# Lora-ver1_0.net
KiCad netlist of a schematic drawn in Altium Designer
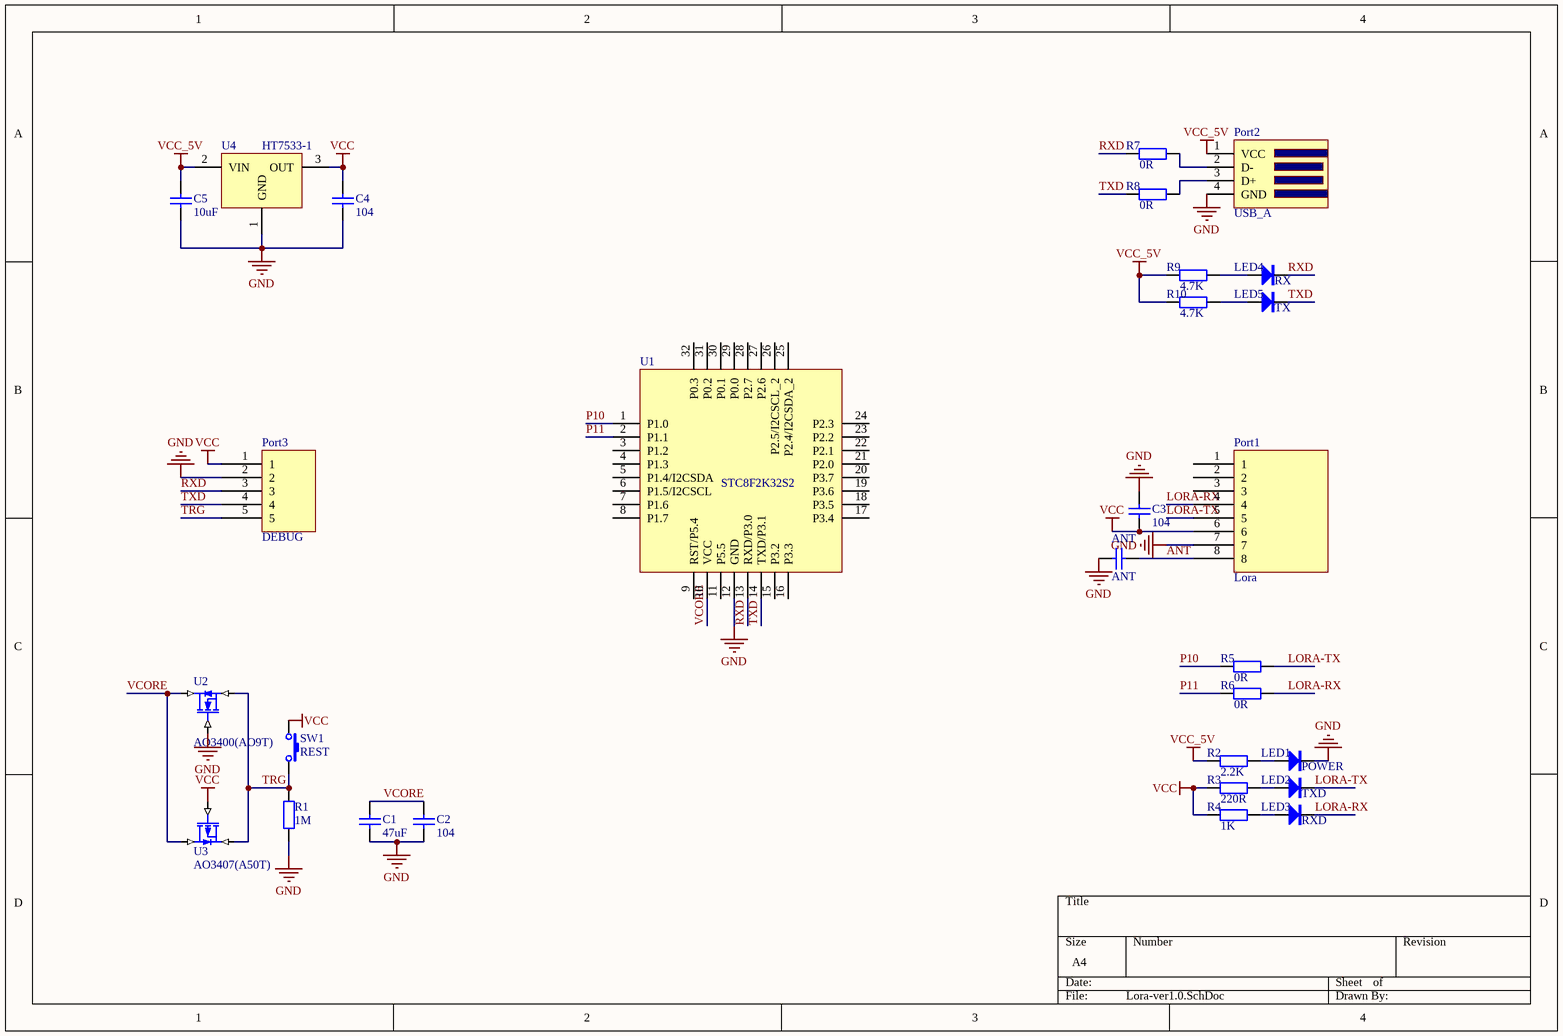
[diagram p0: Lora-ver1.0.SchDoc]

(export (version "E")
  (design (tool "Eeschema 10.0.6"))
  (components
    (comp (ref "ANT")
      (value "ANT")
      (footprint "SWA-KE天线母座")
      (description "Capacitor")
      (fields (field (name "PUBLISHER") "Altium Limited"))
      (libsource (lib "Miscellaneous Devices") (part "Cap"))
    )
    (comp (ref "C1")
      (value "47uF")
      (footprint "0603")
      (description "Capacitor")
      (fields (field (name "PUBLISHER") "Altium Limited"))
      (libsource (lib "Miscellaneous Devices") (part "Cap"))
    )
    (comp (ref "C2")
      (value "104")
      (footprint "0603")
      (description "Capacitor")
      (fields (field (name "PUBLISHER") "Altium Limited"))
      (libsource (lib "Miscellaneous Devices") (part "Cap"))
    )
    (comp (ref "C3")
      (value "104")
      (footprint "0603")
      (description "Capacitor")
      (fields (field (name "PUBLISHER") "Altium Limited"))
      (libsource (lib "Miscellaneous Devices") (part "Cap"))
    )
    (comp (ref "C4")
      (value "104")
      (footprint "0603")
      (description "Capacitor")
      (fields (field (name "PUBLISHER") "Altium Limited"))
      (libsource (lib "Miscellaneous Devices") (part "Cap"))
    )
    (comp (ref "C5")
      (value "10uF")
      (footprint "0603")
      (description "Capacitor")
      (fields (field (name "PUBLISHER") "Altium Limited"))
      (libsource (lib "Miscellaneous Devices") (part "Cap"))
    )
    (comp (ref "LED1")
      (value "POWER")
      (footprint "2.54LED")
      (description "diode")
      (libsource (lib "dajiang SCH -DXP") (part "DIODE"))
    )
    (comp (ref "LED2")
      (value "TXD")
      (footprint "2.54LED")
      (description "diode")
      (libsource (lib "dajiang SCH -DXP") (part "DIODE"))
    )
    (comp (ref "LED3")
      (value "RXD")
      (footprint "2.54LED")
      (description "diode")
      (libsource (lib "dajiang SCH -DXP") (part "DIODE"))
    )
    (comp (ref "LED4")
      (value "RX")
      (footprint "LED-0603")
      (description "diode")
      (libsource (lib "dajiang SCH -DXP") (part "DIODE"))
    )
    (comp (ref "LED5")
      (value "TX")
      (footprint "LED-0603")
      (description "diode")
      (libsource (lib "dajiang SCH -DXP") (part "DIODE"))
    )
    (comp (ref "Port1") (value "Lora") (footprint "LoRa_Usart") (libsource (lib "MYSHC") (part "Lora")))
    (comp (ref "Port2") (value "USB_A") (footprint "USB-A") (libsource (lib "mylib") (part "USB")))
    (comp (ref "Port3") (value "DEBUG") (footprint "STC_DEBUG") (libsource (lib "MYSHC") (part "PIN-5")))
    (comp (ref "R1")
      (value "1M")
      (footprint "0603")
      (description "Resistor")
      (fields (field (name "PUBLISHER") "Altium Limited"))
      (libsource (lib "") (part "Res2_1"))
    )
    (comp (ref "R2")
      (value "2.2K")
      (footprint "0603")
      (description "Resistor")
      (fields (field (name "PUBLISHER") "Altium Limited"))
      (libsource (lib "Miscellaneous Devices") (part "Res2"))
    )
    (comp (ref "R3")
      (value "220R")
      (footprint "0603")
      (description "Resistor")
      (fields (field (name "PUBLISHER") "Altium Limited"))
      (libsource (lib "Miscellaneous Devices") (part "Res2"))
    )
    (comp (ref "R4")
      (value "1K")
      (footprint "0603")
      (description "Resistor")
      (fields (field (name "PUBLISHER") "Altium Limited"))
      (libsource (lib "Miscellaneous Devices") (part "Res2"))
    )
    (comp (ref "R5")
      (value "0R")
      (footprint "0603")
      (description "Resistor")
      (fields (field (name "PUBLISHER") "Altium Limited"))
      (libsource (lib "Miscellaneous Devices") (part "Res2"))
    )
    (comp (ref "R6")
      (value "0R")
      (footprint "0603")
      (description "Resistor")
      (fields (field (name "PUBLISHER") "Altium Limited"))
      (libsource (lib "Miscellaneous Devices") (part "Res2"))
    )
    (comp (ref "R7")
      (value "0R")
      (footprint "0603")
      (description "Resistor")
      (fields (field (name "PUBLISHER") "Altium Limited"))
      (libsource (lib "Miscellaneous Devices") (part "Res2"))
    )
    (comp (ref "R8")
      (value "0R")
      (footprint "0603")
      (description "Resistor")
      (fields (field (name "PUBLISHER") "Altium Limited"))
      (libsource (lib "Miscellaneous Devices") (part "Res2"))
    )
    (comp (ref "R9")
      (value "4.7K")
      (footprint "0603")
      (description "Resistor")
      (fields (field (name "PUBLISHER") "Altium Limited"))
      (libsource (lib "Miscellaneous Devices") (part "Res2"))
    )
    (comp (ref "R10")
      (value "4.7K")
      (footprint "0603")
      (description "Resistor")
      (fields (field (name "PUBLISHER") "Altium Limited"))
      (libsource (lib "Miscellaneous Devices") (part "Res2"))
    )
    (comp (ref "SW1")
      (value "REST")
      (footprint "SW-1")
      (description "key")
      (libsource (lib "dajiang SCH -DXP") (part "SW-P"))
    )
    (comp (ref "U1")
      (value "STC8F2K32S2")
      (footprint "LQPF-32")
      (libsource (lib "mylib") (part "STC8F2K64S2"))
    )
    (comp (ref "U2")
      (value "AO3400(AO9T)")
      (footprint "SOT-23")
      (description "mosfet")
      (libsource (lib "dajiang SCH -DXP") (part "MOSFET-N"))
    )
    (comp (ref "U3")
      (value "AO3407(A50T)")
      (footprint "SOT-23")
      (description "mosfet")
      (libsource (lib "dajiang SCH -DXP") (part "MOSFET-P"))
    )
    (comp (ref "U4") (value "HT7533-1") (footprint "3A5A3D") (libsource (lib "mylib") (part "HT7533-1")))
  )
  (nets
    (net (code "1") (name "/ANT") (class "Default")
      (node (ref "ANT") (pin "1") (pinfunction "1_1") (pintype "passive"))
      (node (ref "Port1") (pin "8") (pinfunction "8_8") (pintype "passive"))
    )
    (net (code "2") (name "/LORA-RX") (class "Default")
      (node (ref "LED3") (pin "2") (pinfunction "2_2") (pintype "passive"))
      (node (ref "Port1") (pin "4") (pinfunction "4_4") (pintype "passive"))
      (node (ref "R6") (pin "1") (pinfunction "1_1") (pintype "passive"))
    )
    (net (code "3") (name "/LORA-TX") (class "Default")
      (node (ref "LED2") (pin "2") (pinfunction "2_2") (pintype "passive"))
      (node (ref "Port1") (pin "5") (pinfunction "5_5") (pintype "passive"))
      (node (ref "R5") (pin "1") (pinfunction "1_1") (pintype "passive"))
    )
    (net (code "4") (name "/P10") (class "Default")
      (node (ref "R5") (pin "2") (pinfunction "2_2") (pintype "passive"))
      (node (ref "U1") (pin "1") (pinfunction "P1.0_1") (pintype "passive"))
    )
    (net (code "5") (name "/P11") (class "Default")
      (node (ref "R6") (pin "2") (pinfunction "2_2") (pintype "passive"))
      (node (ref "U1") (pin "2") (pinfunction "P1.1_2") (pintype "passive"))
    )
    (net (code "6") (name "/RXD") (class "Default")
      (node (ref "LED4") (pin "2") (pinfunction "2_2") (pintype "passive"))
      (node (ref "Port3") (pin "3") (pinfunction "3_3") (pintype "passive"))
      (node (ref "R7") (pin "2") (pinfunction "2_2") (pintype "passive"))
      (node (ref "U1") (pin "13") (pinfunction "RXD/P3.0_13") (pintype "passive"))
    )
    (net (code "7") (name "/TRG") (class "Default")
      (node (ref "Port3") (pin "5") (pinfunction "5_5") (pintype "passive"))
      (node (ref "R1") (pin "2") (pinfunction "2_2") (pintype "passive"))
      (node (ref "SW1") (pin "2") (pinfunction "2_2") (pintype "passive"))
      (node (ref "U2") (pin "2") (pinfunction "D_2") (pintype "input"))
      (node (ref "U3") (pin "2") (pinfunction "S_2") (pintype "input"))
    )
    (net (code "8") (name "/TXD") (class "Default")
      (node (ref "LED5") (pin "2") (pinfunction "2_2") (pintype "passive"))
      (node (ref "Port3") (pin "4") (pinfunction "4_4") (pintype "passive"))
      (node (ref "R8") (pin "2") (pinfunction "2_2") (pintype "passive"))
      (node (ref "U1") (pin "14") (pinfunction "TXD/P3.1_14") (pintype "passive"))
    )
    (net (code "9") (name "/VCORE") (class "Default")
      (node (ref "C1") (pin "2") (pinfunction "2_2") (pintype "passive"))
      (node (ref "C2") (pin "2") (pinfunction "2_2") (pintype "passive"))
      (node (ref "U1") (pin "10") (pinfunction "VCC_10") (pintype "passive"))
      (node (ref "U2") (pin "3") (pinfunction "S_3") (pintype "input"))
      (node (ref "U3") (pin "3") (pinfunction "D_3") (pintype "input"))
    )
    (net (code "10") (name "GND") (class "Default")
      (node (ref "ANT") (pin "2") (pinfunction "2_2") (pintype "passive"))
      (node (ref "C1") (pin "1") (pinfunction "1_1") (pintype "passive"))
      (node (ref "C2") (pin "1") (pinfunction "1_1") (pintype "passive"))
      (node (ref "C3") (pin "1") (pinfunction "1_1") (pintype "passive"))
      (node (ref "C4") (pin "2") (pinfunction "2_2") (pintype "passive"))
      (node (ref "C5") (pin "2") (pinfunction "2_2") (pintype "passive"))
      (node (ref "LED1") (pin "2") (pinfunction "2_2") (pintype "passive"))
      (node (ref "Port1") (pin "7") (pinfunction "7_7") (pintype "passive"))
      (node (ref "Port2") (pin "4") (pinfunction "GND_4") (pintype "passive"))
      (node (ref "Port3") (pin "2") (pinfunction "2_2") (pintype "passive"))
      (node (ref "R1") (pin "1") (pinfunction "1_1") (pintype "passive"))
      (node (ref "U1") (pin "12") (pinfunction "GND_12") (pintype "passive"))
      (node (ref "U2") (pin "1") (pinfunction "G_1") (pintype "input"))
      (node (ref "U4") (pin "1") (pinfunction "GND_1") (pintype "passive"))
    )
    (net (code "11") (name "Net-(LED1-Pad1)") (class "Default")
      (node (ref "LED1") (pin "1") (pinfunction "1_1") (pintype "passive"))
      (node (ref "R2") (pin "1") (pinfunction "1_1") (pintype "passive"))
    )
    (net (code "12") (name "Net-(LED2-Pad1)") (class "Default")
      (node (ref "LED2") (pin "1") (pinfunction "1_1") (pintype "passive"))
      (node (ref "R3") (pin "1") (pinfunction "1_1") (pintype "passive"))
    )
    (net (code "13") (name "Net-(LED3-Pad1)") (class "Default")
      (node (ref "LED3") (pin "1") (pinfunction "1_1") (pintype "passive"))
      (node (ref "R4") (pin "1") (pinfunction "1_1") (pintype "passive"))
    )
    (net (code "14") (name "Net-(LED4-Pad1)") (class "Default")
      (node (ref "LED4") (pin "1") (pinfunction "1_1") (pintype "passive"))
      (node (ref "R9") (pin "1") (pinfunction "1_1") (pintype "passive"))
    )
    (net (code "15") (name "Net-(LED5-Pad1)") (class "Default")
      (node (ref "LED5") (pin "1") (pinfunction "1_1") (pintype "passive"))
      (node (ref "R10") (pin "1") (pinfunction "1_1") (pintype "passive"))
    )
    (net (code "16") (name "Net-(Port2-D+)") (class "Default")
      (node (ref "Port2") (pin "3") (pinfunction "D+_3") (pintype "passive"))
      (node (ref "R8") (pin "1") (pinfunction "1_1") (pintype "passive"))
    )
    (net (code "17") (name "Net-(Port2-D-)") (class "Default")
      (node (ref "Port2") (pin "2") (pinfunction "D-_2") (pintype "passive"))
      (node (ref "R7") (pin "1") (pinfunction "1_1") (pintype "passive"))
    )
    (net (code "18") (name "VCC") (class "Default")
      (node (ref "C3") (pin "2") (pinfunction "2_2") (pintype "passive"))
      (node (ref "C4") (pin "1") (pinfunction "1_1") (pintype "passive"))
      (node (ref "Port1") (pin "6") (pinfunction "6_6") (pintype "passive"))
      (node (ref "Port3") (pin "1") (pinfunction "1_1") (pintype "passive"))
      (node (ref "R3") (pin "2") (pinfunction "2_2") (pintype "passive"))
      (node (ref "R4") (pin "2") (pinfunction "2_2") (pintype "passive"))
      (node (ref "SW1") (pin "1") (pinfunction "1_1") (pintype "passive"))
      (node (ref "U3") (pin "1") (pinfunction "G_1") (pintype "input"))
      (node (ref "U4") (pin "3") (pinfunction "OUT_3") (pintype "passive"))
    )
    (net (code "19") (name "VCC_5V") (class "Default")
      (node (ref "C5") (pin "1") (pinfunction "1_1") (pintype "passive"))
      (node (ref "Port2") (pin "1") (pinfunction "VCC_1") (pintype "passive"))
      (node (ref "R10") (pin "2") (pinfunction "2_2") (pintype "passive"))
      (node (ref "R2") (pin "2") (pinfunction "2_2") (pintype "passive"))
      (node (ref "R9") (pin "2") (pinfunction "2_2") (pintype "passive"))
      (node (ref "U4") (pin "2") (pinfunction "VIN_2") (pintype "passive"))
    )
    (net (code "20") (name "unconnected-(Port1-Pad1)") (class "Default")
      (node (ref "Port1") (pin "1") (pinfunction "1_1") (pintype "passive"))
    )
    (net (code "21") (name "unconnected-(Port1-Pad2)") (class "Default")
      (node (ref "Port1") (pin "2") (pinfunction "2_2") (pintype "passive"))
    )
    (net (code "22") (name "unconnected-(Port1-Pad3)") (class "Default")
      (node (ref "Port1") (pin "3") (pinfunction "3_3") (pintype "passive"))
    )
    (net (code "23") (name "unconnected-(U1-P0.0-Pad29)") (class "Default")
      (node (ref "U1") (pin "29") (pinfunction "P0.0_29") (pintype "passive"))
    )
    (net (code "24") (name "unconnected-(U1-P0.1-Pad30)") (class "Default")
      (node (ref "U1") (pin "30") (pinfunction "P0.1_30") (pintype "passive"))
    )
    (net (code "25") (name "unconnected-(U1-P0.2-Pad31)") (class "Default")
      (node (ref "U1") (pin "31") (pinfunction "P0.2_31") (pintype "passive"))
    )
    (net (code "26") (name "unconnected-(U1-P0.3-Pad32)") (class "Default")
      (node (ref "U1") (pin "32") (pinfunction "P0.3_32") (pintype "passive"))
    )
    (net (code "27") (name "unconnected-(U1-P1.2-Pad3)") (class "Default")
      (node (ref "U1") (pin "3") (pinfunction "P1.2_3") (pintype "passive"))
    )
    (net (code "28") (name "unconnected-(U1-P1.3-Pad4)") (class "Default")
      (node (ref "U1") (pin "4") (pinfunction "P1.3_4") (pintype "passive"))
    )
    (net (code "29") (name "unconnected-(U1-P1.4{slash}I2CSDA-Pad5)") (class "Default")
      (node (ref "U1") (pin "5") (pinfunction "P1.4/I2CSDA_5") (pintype "passive"))
    )
    (net (code "30") (name "unconnected-(U1-P1.5{slash}I2CSCL-Pad6)") (class "Default")
      (node (ref "U1") (pin "6") (pinfunction "P1.5/I2CSCL_6") (pintype "passive"))
    )
    (net (code "31") (name "unconnected-(U1-P1.6-Pad7)") (class "Default")
      (node (ref "U1") (pin "7") (pinfunction "P1.6_7") (pintype "passive"))
    )
    (net (code "32") (name "unconnected-(U1-P1.7-Pad8)") (class "Default")
      (node (ref "U1") (pin "8") (pinfunction "P1.7_8") (pintype "passive"))
    )
    (net (code "33") (name "unconnected-(U1-P2.0-Pad21)") (class "Default")
      (node (ref "U1") (pin "21") (pinfunction "P2.0_21") (pintype "passive"))
    )
    (net (code "34") (name "unconnected-(U1-P2.1-Pad22)") (class "Default")
      (node (ref "U1") (pin "22") (pinfunction "P2.1_22") (pintype "passive"))
    )
    (net (code "35") (name "unconnected-(U1-P2.2-Pad23)") (class "Default")
      (node (ref "U1") (pin "23") (pinfunction "P2.2_23") (pintype "passive"))
    )
    (net (code "36") (name "unconnected-(U1-P2.3-Pad24)") (class "Default")
      (node (ref "U1") (pin "24") (pinfunction "P2.3_24") (pintype "passive"))
    )
    (net (code "37") (name "unconnected-(U1-P2.4{slash}I2CSDA_2-Pad25)") (class "Default")
      (node (ref "U1") (pin "25") (pinfunction "P2.4/I2CSDA_2_25") (pintype "passive"))
    )
    (net (code "38") (name "unconnected-(U1-P2.5{slash}I2CSCL_2-Pad26)") (class "Default")
      (node (ref "U1") (pin "26") (pinfunction "P2.5/I2CSCL_2_26") (pintype "passive"))
    )
    (net (code "39") (name "unconnected-(U1-P2.6-Pad27)") (class "Default")
      (node (ref "U1") (pin "27") (pinfunction "P2.6_27") (pintype "passive"))
    )
    (net (code "40") (name "unconnected-(U1-P2.7-Pad28)") (class "Default")
      (node (ref "U1") (pin "28") (pinfunction "P2.7_28") (pintype "passive"))
    )
    (net (code "41") (name "unconnected-(U1-P3.2-Pad15)") (class "Default")
      (node (ref "U1") (pin "15") (pinfunction "P3.2_15") (pintype "passive"))
    )
    (net (code "42") (name "unconnected-(U1-P3.3-Pad16)") (class "Default")
      (node (ref "U1") (pin "16") (pinfunction "P3.3_16") (pintype "passive"))
    )
    (net (code "43") (name "unconnected-(U1-P3.4-Pad17)") (class "Default")
      (node (ref "U1") (pin "17") (pinfunction "P3.4_17") (pintype "passive"))
    )
    (net (code "44") (name "unconnected-(U1-P3.5-Pad18)") (class "Default")
      (node (ref "U1") (pin "18") (pinfunction "P3.5_18") (pintype "passive"))
    )
    (net (code "45") (name "unconnected-(U1-P3.6-Pad19)") (class "Default")
      (node (ref "U1") (pin "19") (pinfunction "P3.6_19") (pintype "passive"))
    )
    (net (code "46") (name "unconnected-(U1-P3.7-Pad20)") (class "Default")
      (node (ref "U1") (pin "20") (pinfunction "P3.7_20") (pintype "passive"))
    )
    (net (code "47") (name "unconnected-(U1-P5.5-Pad11)") (class "Default")
      (node (ref "U1") (pin "11") (pinfunction "P5.5_11") (pintype "passive"))
    )
    (net (code "48") (name "unconnected-(U1-RST{slash}P5.4-Pad9)") (class "Default")
      (node (ref "U1") (pin "9") (pinfunction "RST/P5.4_9") (pintype "passive"))
    )
  )
)
